# V__2.net
KiCad netlist of a schematic drawn in Altium Designer
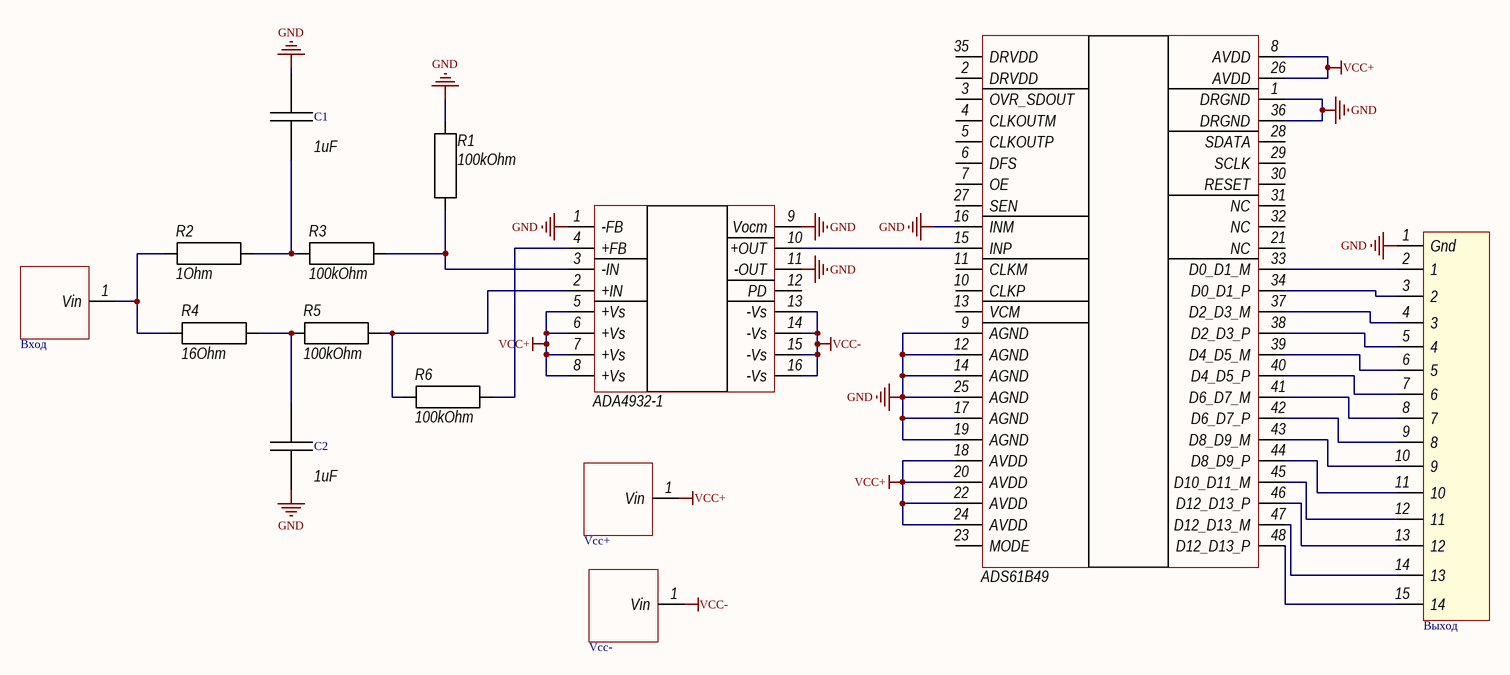
[diagram p0: Принципиальная схема_V_№2.SchDoc]

(export (version "E")
  (design (tool "Eeschema 10.0.6"))
  (components
    (comp (ref "*") (value "Выход") (footprint "Выход") (libsource (lib "Library_V2") (part "Выход")))
    (comp (ref "ADA4932-1")
      (value "ADA4932-1")
      (footprint "CP-16-2")
      (libsource (lib "Library_V2") (part "ADA4932-1"))
    )
    (comp (ref "ADS61B49")
      (value "ADS61B49")
      (footprint "VQFN-48")
      (libsource (lib "Library_V2") (part "ADS61B49"))
    )
    (comp (ref "C1")
      (value "1uF")
      (footprint "Capasitor10X23")
      (libsource (lib "Library_V2") (part "Capasitor"))
    )
    (comp (ref "C2")
      (value "1uF")
      (footprint "Capasitor10X23")
      (libsource (lib "Library_V2") (part "Capasitor"))
    )
    (comp (ref "R1")
      (value "100kOhm")
      (footprint "SMD 0402")
      (libsource (lib "Library_V2") (part "Resistor"))
    )
    (comp (ref "R2") (value "1Ohm") (footprint "SMD 0402") (libsource (lib "Library_V2") (part "Resistor")))
    (comp (ref "R3")
      (value "100kOhm")
      (footprint "SMD 0402")
      (libsource (lib "Library_V2") (part "Resistor"))
    )
    (comp (ref "R4") (value "16Ohm") (footprint "SMD 0402") (libsource (lib "Library_V2") (part "Resistor")))
    (comp (ref "R5")
      (value "100kOhm")
      (footprint "SMD 0402")
      (libsource (lib "Library_V2") (part "Resistor"))
    )
    (comp (ref "R6")
      (value "100kOhm")
      (footprint "SMD 0402")
      (libsource (lib "Library_V2") (part "Resistor"))
    )
    (comp (ref "Vcc+") (value "Vcc+") (footprint "Вход") (libsource (lib "Library_V2") (part "Вход")))
    (comp (ref "Vcc-") (value "Vcc-") (footprint "Вход") (libsource (lib "Library_V2") (part "Вход")))
    (comp (ref "Vin") (value "Вход") (footprint "Вход") (libsource (lib "Library_V2") (part "Вход")))
  )
  (nets
    (net (code "1") (name "GND") (class "Default")
      (node (ref "*") (pin "1") (pinfunction "Gnd_1") (pintype "passive"))
      (node (ref "ADA4932-1") (pin "1") (pinfunction "-FB_1") (pintype "passive"))
      (node (ref "ADA4932-1") (pin "11") (pinfunction "-OUT_11") (pintype "passive"))
      (node (ref "ADA4932-1") (pin "9") (pinfunction "Vocm_9") (pintype "passive"))
      (node (ref "ADS61B49") (pin "1") (pinfunction "DRGND_1") (pintype "passive"))
      (node (ref "ADS61B49") (pin "12") (pinfunction "AGND_12") (pintype "passive"))
      (node (ref "ADS61B49") (pin "14") (pinfunction "AGND_14") (pintype "passive"))
      (node (ref "ADS61B49") (pin "16") (pinfunction "INM_16") (pintype "passive"))
      (node (ref "ADS61B49") (pin "17") (pinfunction "AGND_17") (pintype "passive"))
      (node (ref "ADS61B49") (pin "19") (pinfunction "AGND_19") (pintype "passive"))
      (node (ref "ADS61B49") (pin "25") (pinfunction "AGND_25") (pintype "passive"))
      (node (ref "ADS61B49") (pin "36") (pinfunction "DRGND_36") (pintype "passive"))
      (node (ref "ADS61B49") (pin "9") (pinfunction "AGND_9") (pintype "passive"))
      (node (ref "C1") (pin "1") (pinfunction "0_1") (pintype "passive"))
      (node (ref "C2") (pin "2") (pinfunction "1_2") (pintype "passive"))
      (node (ref "R1") (pin "2") (pintype "passive"))
    )
    (net (code "2") (name "Net-(*-1)") (class "Default")
      (node (ref "*") (pin "2") (pinfunction "1_2") (pintype "passive"))
      (node (ref "ADS61B49") (pin "33") (pinfunction "D0_D1_M_33") (pintype "passive"))
    )
    (net (code "3") (name "Net-(*-2)") (class "Default")
      (node (ref "*") (pin "3") (pinfunction "2_3") (pintype "passive"))
      (node (ref "ADS61B49") (pin "34") (pinfunction "D0_D1_P_34") (pintype "passive"))
    )
    (net (code "4") (name "Net-(*-3)") (class "Default")
      (node (ref "*") (pin "4") (pinfunction "3_4") (pintype "passive"))
      (node (ref "ADS61B49") (pin "37") (pinfunction "D2_D3_M_37") (pintype "passive"))
    )
    (net (code "5") (name "Net-(*-4)") (class "Default")
      (node (ref "*") (pin "5") (pinfunction "4_5") (pintype "passive"))
      (node (ref "ADS61B49") (pin "38") (pinfunction "D2_D3_P_38") (pintype "passive"))
    )
    (net (code "6") (name "Net-(*-5)") (class "Default")
      (node (ref "*") (pin "6") (pinfunction "5_6") (pintype "passive"))
      (node (ref "ADS61B49") (pin "39") (pinfunction "D4_D5_M_39") (pintype "passive"))
    )
    (net (code "7") (name "Net-(*-6)") (class "Default")
      (node (ref "*") (pin "7") (pinfunction "6_7") (pintype "passive"))
      (node (ref "ADS61B49") (pin "40") (pinfunction "D4_D5_P_40") (pintype "passive"))
    )
    (net (code "8") (name "Net-(*-7)") (class "Default")
      (node (ref "*") (pin "8") (pinfunction "7_8") (pintype "passive"))
      (node (ref "ADS61B49") (pin "41") (pinfunction "D6_D7_M_41") (pintype "passive"))
    )
    (net (code "9") (name "Net-(*-8)") (class "Default")
      (node (ref "*") (pin "9") (pinfunction "8_9") (pintype "passive"))
      (node (ref "ADS61B49") (pin "42") (pinfunction "D6_D7_P_42") (pintype "passive"))
    )
    (net (code "10") (name "Net-(*-9)") (class "Default")
      (node (ref "*") (pin "10") (pinfunction "9_10") (pintype "passive"))
      (node (ref "ADS61B49") (pin "43") (pinfunction "D8_D9_M_43") (pintype "passive"))
    )
    (net (code "11") (name "Net-(*-10)") (class "Default")
      (node (ref "*") (pin "11") (pinfunction "10_11") (pintype "passive"))
      (node (ref "ADS61B49") (pin "44") (pinfunction "D8_D9_P_44") (pintype "passive"))
    )
    (net (code "12") (name "Net-(*-11)") (class "Default")
      (node (ref "*") (pin "12") (pinfunction "11_12") (pintype "passive"))
      (node (ref "ADS61B49") (pin "45") (pinfunction "D10_D11_M_45") (pintype "passive"))
    )
    (net (code "13") (name "Net-(*-12)") (class "Default")
      (node (ref "*") (pin "13") (pinfunction "12_13") (pintype "passive"))
      (node (ref "ADS61B49") (pin "46") (pinfunction "D12_D13_P_46") (pintype "passive"))
    )
    (net (code "14") (name "Net-(*-13)") (class "Default")
      (node (ref "*") (pin "14") (pinfunction "13_14") (pintype "passive"))
      (node (ref "ADS61B49") (pin "47") (pinfunction "D12_D13_M_47") (pintype "passive"))
    )
    (net (code "15") (name "Net-(*-14)") (class "Default")
      (node (ref "*") (pin "15") (pinfunction "14_15") (pintype "passive"))
      (node (ref "ADS61B49") (pin "48") (pinfunction "D12_D13_P_48") (pintype "passive"))
    )
    (net (code "16") (name "Net-(ADA4932-1-+FB)") (class "Default")
      (node (ref "ADA4932-1") (pin "4") (pinfunction "+FB_4") (pintype "passive"))
      (node (ref "R6") (pin "2") (pintype "passive"))
    )
    (net (code "17") (name "Net-(ADA4932-1-+IN)") (class "Default")
      (node (ref "ADA4932-1") (pin "2") (pinfunction "+IN_2") (pintype "passive"))
      (node (ref "R5") (pin "2") (pintype "passive"))
      (node (ref "R6") (pin "1") (pintype "passive"))
    )
    (net (code "18") (name "Net-(ADA4932-1-+OUT)") (class "Default")
      (node (ref "ADA4932-1") (pin "10") (pinfunction "+OUT_10") (pintype "passive"))
      (node (ref "ADS61B49") (pin "15") (pinfunction "INP_15") (pintype "passive"))
    )
    (net (code "19") (name "Net-(ADA4932-1--IN)") (class "Default")
      (node (ref "ADA4932-1") (pin "3") (pinfunction "-IN_3") (pintype "passive"))
      (node (ref "R1") (pin "1") (pintype "passive"))
      (node (ref "R3") (pin "2") (pintype "passive"))
    )
    (net (code "20") (name "Net-(C1-1)") (class "Default")
      (node (ref "C1") (pin "2") (pinfunction "1_2") (pintype "passive"))
      (node (ref "R2") (pin "2") (pintype "passive"))
      (node (ref "R3") (pin "1") (pintype "passive"))
    )
    (net (code "21") (name "Net-(C2-0)") (class "Default")
      (node (ref "C2") (pin "1") (pinfunction "0_1") (pintype "passive"))
      (node (ref "R4") (pin "2") (pintype "passive"))
      (node (ref "R5") (pin "1") (pintype "passive"))
    )
    (net (code "22") (name "Net-(Vin-Vin)") (class "Default")
      (node (ref "R2") (pin "1") (pintype "passive"))
      (node (ref "R4") (pin "1") (pintype "passive"))
      (node (ref "Vin") (pin "1") (pinfunction "Vin_1") (pintype "passive"))
    )
    (net (code "23") (name "VCC+") (class "Default")
      (node (ref "ADA4932-1") (pin "5") (pinfunction "+Vs_5") (pintype "passive"))
      (node (ref "ADA4932-1") (pin "6") (pinfunction "+Vs_6") (pintype "passive"))
      (node (ref "ADA4932-1") (pin "7") (pinfunction "+Vs_7") (pintype "passive"))
      (node (ref "ADA4932-1") (pin "8") (pinfunction "+Vs_8") (pintype "passive"))
      (node (ref "ADS61B49") (pin "18") (pinfunction "AVDD_18") (pintype "passive"))
      (node (ref "ADS61B49") (pin "20") (pinfunction "AVDD_20") (pintype "passive"))
      (node (ref "ADS61B49") (pin "22") (pinfunction "AVDD_22") (pintype "passive"))
      (node (ref "ADS61B49") (pin "24") (pinfunction "AVDD_24") (pintype "passive"))
      (node (ref "ADS61B49") (pin "26") (pinfunction "AVDD_26") (pintype "passive"))
      (node (ref "ADS61B49") (pin "8") (pinfunction "AVDD_8") (pintype "passive"))
      (node (ref "Vcc+") (pin "1") (pinfunction "Vin_1") (pintype "passive"))
    )
    (net (code "24") (name "VCC-") (class "Default")
      (node (ref "ADA4932-1") (pin "13") (pinfunction "-Vs_13") (pintype "passive"))
      (node (ref "ADA4932-1") (pin "14") (pinfunction "-Vs_14") (pintype "passive"))
      (node (ref "ADA4932-1") (pin "15") (pinfunction "-Vs_15") (pintype "passive"))
      (node (ref "ADA4932-1") (pin "16") (pinfunction "-Vs_16") (pintype "passive"))
      (node (ref "Vcc-") (pin "1") (pinfunction "Vin_1") (pintype "passive"))
    )
    (net (code "25") (name "unconnected-(ADA4932-1-PD-Pad12)") (class "Default")
      (node (ref "ADA4932-1") (pin "12") (pinfunction "PD_12") (pintype "passive"))
    )
    (net (code "26") (name "unconnected-(ADS61B49-CLKM-Pad11)") (class "Default")
      (node (ref "ADS61B49") (pin "11") (pinfunction "CLKM_11") (pintype "passive"))
    )
    (net (code "27") (name "unconnected-(ADS61B49-CLKOUTM-Pad4)") (class "Default")
      (node (ref "ADS61B49") (pin "4") (pinfunction "CLKOUTM_4") (pintype "passive"))
    )
    (net (code "28") (name "unconnected-(ADS61B49-CLKOUTP-Pad5)") (class "Default")
      (node (ref "ADS61B49") (pin "5") (pinfunction "CLKOUTP_5") (pintype "passive"))
    )
    (net (code "29") (name "unconnected-(ADS61B49-CLKP-Pad10)") (class "Default")
      (node (ref "ADS61B49") (pin "10") (pinfunction "CLKP_10") (pintype "passive"))
    )
    (net (code "30") (name "unconnected-(ADS61B49-DFS-Pad6)") (class "Default")
      (node (ref "ADS61B49") (pin "6") (pinfunction "DFS_6") (pintype "passive"))
    )
    (net (code "31") (name "unconnected-(ADS61B49-DRVDD-Pad2)") (class "Default")
      (node (ref "ADS61B49") (pin "2") (pinfunction "DRVDD_2") (pintype "passive"))
    )
    (net (code "32") (name "unconnected-(ADS61B49-DRVDD-Pad35)") (class "Default")
      (node (ref "ADS61B49") (pin "35") (pinfunction "DRVDD_35") (pintype "passive"))
    )
    (net (code "33") (name "unconnected-(ADS61B49-MODE-Pad23)") (class "Default")
      (node (ref "ADS61B49") (pin "23") (pinfunction "MODE_23") (pintype "passive"))
    )
    (net (code "34") (name "unconnected-(ADS61B49-NC-Pad21)") (class "Default")
      (node (ref "ADS61B49") (pin "21") (pinfunction "NC_21") (pintype "passive"))
    )
    (net (code "35") (name "unconnected-(ADS61B49-NC-Pad31)") (class "Default")
      (node (ref "ADS61B49") (pin "31") (pinfunction "NC_31") (pintype "passive"))
    )
    (net (code "36") (name "unconnected-(ADS61B49-NC-Pad32)") (class "Default")
      (node (ref "ADS61B49") (pin "32") (pinfunction "NC_32") (pintype "passive"))
    )
    (net (code "37") (name "unconnected-(ADS61B49-OE-Pad7)") (class "Default")
      (node (ref "ADS61B49") (pin "7") (pinfunction "OE_7") (pintype "passive"))
    )
    (net (code "38") (name "unconnected-(ADS61B49-OVR_SDOUT-Pad3)") (class "Default")
      (node (ref "ADS61B49") (pin "3") (pinfunction "OVR_SDOUT_3") (pintype "passive"))
    )
    (net (code "39") (name "unconnected-(ADS61B49-RESET-Pad30)") (class "Default")
      (node (ref "ADS61B49") (pin "30") (pinfunction "RESET_30") (pintype "passive"))
    )
    (net (code "40") (name "unconnected-(ADS61B49-SCLK-Pad29)") (class "Default")
      (node (ref "ADS61B49") (pin "29") (pinfunction "SCLK_29") (pintype "passive"))
    )
    (net (code "41") (name "unconnected-(ADS61B49-SDATA-Pad28)") (class "Default")
      (node (ref "ADS61B49") (pin "28") (pinfunction "SDATA_28") (pintype "passive"))
    )
    (net (code "42") (name "unconnected-(ADS61B49-SEN-Pad27)") (class "Default")
      (node (ref "ADS61B49") (pin "27") (pinfunction "SEN_27") (pintype "passive"))
    )
    (net (code "43") (name "unconnected-(ADS61B49-VCM-Pad13)") (class "Default")
      (node (ref "ADS61B49") (pin "13") (pinfunction "VCM_13") (pintype "passive"))
    )
  )
)
